# CLK_Mezzanine.net
KiCad netlist of a schematic drawn in Altium Designer
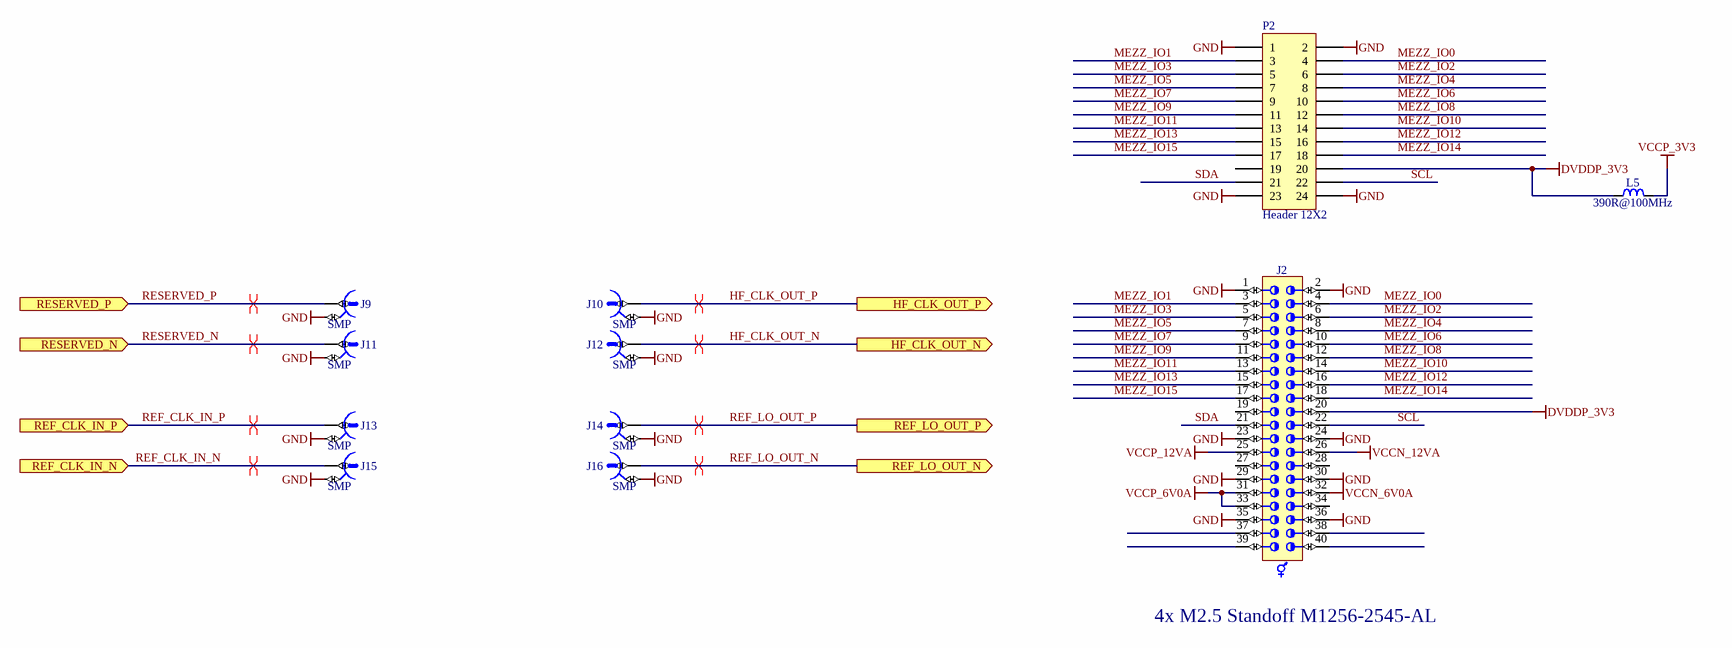
[diagram p0: CLK_Mezzanine.SchDoc]

(export (version "E")
  (design (tool "Eeschema 10.0.6"))
  (components
    (comp (ref "J2")
      (value "~")
      (footprint "SAMTEC_LSS-120-03-L-DV-A")
      (description "Connector 40 Hermaphroditic")
      (fields
        (field (name "PART NUMBER") "SAMTEC_LSS-120-03-L-DV-A")
        (field (name "MANUFACTURER") "SAMTEC")
        (field (name "AUTHOR") "CERN DEM JMW")
      )
      (libsource (lib "Connectors") (part "Connector 40 Hermaphroditic"))
    )
    (comp (ref "J9")
      (value "SMP")
      (footprint "MOLEX_85305-0232")
      (fields
        (field (name "PART NUMBER") "MOLEX_85305-0232")
        (field (name "MANUFACTURER") "MOLEX")
        (field (name "MANUFACTURER PART NUMBER") "85305-0232")
        (field (name "AUTHOR") "CERN DEM JMW")
      )
      (libsource (lib "") (part "Coax_1Male_1Shield_1"))
    )
    (comp (ref "J10")
      (value "SMP")
      (footprint "MOLEX_85305-0232")
      (fields
        (field (name "PART NUMBER") "MOLEX_85305-0232")
        (field (name "MANUFACTURER") "MOLEX")
        (field (name "MANUFACTURER PART NUMBER") "85305-0232")
        (field (name "AUTHOR") "CERN DEM JMW")
      )
      (libsource (lib "Connectors") (part "Coax_1Male_1Shield"))
    )
    (comp (ref "J11")
      (value "SMP")
      (footprint "MOLEX_85305-0232")
      (fields
        (field (name "PART NUMBER") "MOLEX_85305-0232")
        (field (name "MANUFACTURER") "MOLEX")
        (field (name "MANUFACTURER PART NUMBER") "85305-0232")
        (field (name "AUTHOR") "CERN DEM JMW")
      )
      (libsource (lib "") (part "Coax_1Male_1Shield_1"))
    )
    (comp (ref "J12")
      (value "SMP")
      (footprint "MOLEX_85305-0232")
      (fields
        (field (name "PART NUMBER") "MOLEX_85305-0232")
        (field (name "MANUFACTURER") "MOLEX")
        (field (name "MANUFACTURER PART NUMBER") "85305-0232")
        (field (name "AUTHOR") "CERN DEM JMW")
      )
      (libsource (lib "Connectors") (part "Coax_1Male_1Shield"))
    )
    (comp (ref "J13")
      (value "SMP")
      (footprint "MOLEX_85305-0232")
      (fields
        (field (name "PART NUMBER") "MOLEX_85305-0232")
        (field (name "MANUFACTURER") "MOLEX")
        (field (name "MANUFACTURER PART NUMBER") "85305-0232")
        (field (name "AUTHOR") "CERN DEM JMW")
      )
      (libsource (lib "") (part "Coax_1Male_1Shield_1"))
    )
    (comp (ref "J14")
      (value "SMP")
      (footprint "MOLEX_85305-0232")
      (fields
        (field (name "PART NUMBER") "MOLEX_85305-0232")
        (field (name "MANUFACTURER") "MOLEX")
        (field (name "MANUFACTURER PART NUMBER") "85305-0232")
        (field (name "AUTHOR") "CERN DEM JMW")
      )
      (libsource (lib "Connectors") (part "Coax_1Male_1Shield"))
    )
    (comp (ref "J15")
      (value "SMP")
      (footprint "MOLEX_85305-0232")
      (fields
        (field (name "PART NUMBER") "MOLEX_85305-0232")
        (field (name "MANUFACTURER") "MOLEX")
        (field (name "MANUFACTURER PART NUMBER") "85305-0232")
        (field (name "AUTHOR") "CERN DEM JMW")
      )
      (libsource (lib "") (part "Coax_1Male_1Shield_1"))
    )
    (comp (ref "J16")
      (value "SMP")
      (footprint "MOLEX_85305-0232")
      (fields
        (field (name "PART NUMBER") "MOLEX_85305-0232")
        (field (name "MANUFACTURER") "MOLEX")
        (field (name "MANUFACTURER PART NUMBER") "85305-0232")
        (field (name "AUTHOR") "CERN DEM JMW")
      )
      (libsource (lib "Connectors") (part "Coax_1Male_1Shield"))
    )
    (comp (ref "L5")
      (value "390R@100MHz")
      (footprint "INDC1608X95N")
      (description "Inductor")
      (fields
        (field (name "PART NUMBER") "IND0603_TDK_MPZ1608R391A")
        (field (name "POWER") "1.2A")
        (field (name "AUTHOR") "CERN DEM JLC")
      )
      (libsource (lib "Inductors & Transformers") (part "Inductor"))
    )
    (comp (ref "P2")
      (value "Header 12X2")
      (footprint "HDR2X12")
      (description "Header, 12-Pin, Dual row")
      (fields (field (name "PUBLISHER") "Altium Limited"))
      (libsource (lib "Miscellaneous Connectors") (part "Header 12X2"))
    )
  )
  (nets
    (net (code "1") (name "/HF_CLK_OUT_N") (class "Default")
      (node (ref "J12") (pin "1") (pinfunction "1_1") (pintype "bidirectional"))
    )
    (net (code "2") (name "/HF_CLK_OUT_P") (class "Default")
      (node (ref "J10") (pin "1") (pinfunction "1_1") (pintype "bidirectional"))
    )
    (net (code "3") (name "/MEZZ_IO0") (class "Default")
      (node (ref "J2") (pin "4") (pinfunction "4_4") (pintype "bidirectional"))
      (node (ref "P2") (pin "4") (pinfunction "4_4") (pintype "passive"))
    )
    (net (code "4") (name "/MEZZ_IO1") (class "Default")
      (node (ref "J2") (pin "3") (pinfunction "3_3") (pintype "bidirectional"))
      (node (ref "P2") (pin "3") (pinfunction "3_3") (pintype "passive"))
    )
    (net (code "5") (name "/MEZZ_IO2") (class "Default")
      (node (ref "J2") (pin "6") (pinfunction "6_6") (pintype "bidirectional"))
      (node (ref "P2") (pin "6") (pinfunction "6_6") (pintype "passive"))
    )
    (net (code "6") (name "/MEZZ_IO3") (class "Default")
      (node (ref "J2") (pin "5") (pinfunction "5_5") (pintype "bidirectional"))
      (node (ref "P2") (pin "5") (pinfunction "5_5") (pintype "passive"))
    )
    (net (code "7") (name "/MEZZ_IO4") (class "Default")
      (node (ref "J2") (pin "8") (pinfunction "8_8") (pintype "bidirectional"))
      (node (ref "P2") (pin "8") (pinfunction "8_8") (pintype "passive"))
    )
    (net (code "8") (name "/MEZZ_IO5") (class "Default")
      (node (ref "J2") (pin "7") (pinfunction "7_7") (pintype "bidirectional"))
      (node (ref "P2") (pin "7") (pinfunction "7_7") (pintype "passive"))
    )
    (net (code "9") (name "/MEZZ_IO6") (class "Default")
      (node (ref "J2") (pin "10") (pinfunction "10_10") (pintype "bidirectional"))
      (node (ref "P2") (pin "10") (pinfunction "10_10") (pintype "passive"))
    )
    (net (code "10") (name "/MEZZ_IO7") (class "Default")
      (node (ref "J2") (pin "9") (pinfunction "9_9") (pintype "bidirectional"))
      (node (ref "P2") (pin "9") (pinfunction "9_9") (pintype "passive"))
    )
    (net (code "11") (name "/MEZZ_IO8") (class "Default")
      (node (ref "J2") (pin "12") (pinfunction "12_12") (pintype "bidirectional"))
      (node (ref "P2") (pin "12") (pinfunction "12_12") (pintype "passive"))
    )
    (net (code "12") (name "/MEZZ_IO9") (class "Default")
      (node (ref "J2") (pin "11") (pinfunction "11_11") (pintype "bidirectional"))
      (node (ref "P2") (pin "11") (pinfunction "11_11") (pintype "passive"))
    )
    (net (code "13") (name "/MEZZ_IO10") (class "Default")
      (node (ref "J2") (pin "14") (pinfunction "14_14") (pintype "bidirectional"))
      (node (ref "P2") (pin "14") (pinfunction "14_14") (pintype "passive"))
    )
    (net (code "14") (name "/MEZZ_IO11") (class "Default")
      (node (ref "J2") (pin "13") (pinfunction "13_13") (pintype "bidirectional"))
      (node (ref "P2") (pin "13") (pinfunction "13_13") (pintype "passive"))
    )
    (net (code "15") (name "/MEZZ_IO12") (class "Default")
      (node (ref "J2") (pin "16") (pinfunction "16_16") (pintype "bidirectional"))
      (node (ref "P2") (pin "16") (pinfunction "16_16") (pintype "passive"))
    )
    (net (code "16") (name "/MEZZ_IO13") (class "Default")
      (node (ref "J2") (pin "15") (pinfunction "15_15") (pintype "bidirectional"))
      (node (ref "P2") (pin "15") (pinfunction "15_15") (pintype "passive"))
    )
    (net (code "17") (name "/MEZZ_IO14") (class "Default")
      (node (ref "J2") (pin "18") (pinfunction "18_18") (pintype "bidirectional"))
      (node (ref "P2") (pin "18") (pinfunction "18_18") (pintype "passive"))
    )
    (net (code "18") (name "/MEZZ_IO15") (class "Default")
      (node (ref "J2") (pin "17") (pinfunction "17_17") (pintype "bidirectional"))
      (node (ref "P2") (pin "17") (pinfunction "17_17") (pintype "passive"))
    )
    (net (code "19") (name "/REF_CLK_IN_N") (class "Default")
      (node (ref "J15") (pin "1") (pinfunction "1_1") (pintype "bidirectional"))
    )
    (net (code "20") (name "/REF_CLK_IN_P") (class "Default")
      (node (ref "J13") (pin "1") (pinfunction "1_1") (pintype "bidirectional"))
    )
    (net (code "21") (name "/REF_LO_OUT_N") (class "Default")
      (node (ref "J16") (pin "1") (pinfunction "1_1") (pintype "bidirectional"))
    )
    (net (code "22") (name "/REF_LO_OUT_P") (class "Default")
      (node (ref "J14") (pin "1") (pinfunction "1_1") (pintype "bidirectional"))
    )
    (net (code "23") (name "/RESERVED_N") (class "Default")
      (node (ref "J11") (pin "1") (pinfunction "1_1") (pintype "bidirectional"))
    )
    (net (code "24") (name "/RESERVED_P") (class "Default")
      (node (ref "J9") (pin "1") (pinfunction "1_1") (pintype "bidirectional"))
    )
    (net (code "25") (name "/SCL") (class "Default")
      (node (ref "J2") (pin "22") (pinfunction "22_22") (pintype "bidirectional"))
      (node (ref "P2") (pin "22") (pinfunction "22_22") (pintype "passive"))
    )
    (net (code "26") (name "/SDA") (class "Default")
      (node (ref "J2") (pin "21") (pinfunction "21_21") (pintype "bidirectional"))
      (node (ref "P2") (pin "21") (pinfunction "21_21") (pintype "passive"))
    )
    (net (code "27") (name "DVDDP_3V3") (class "Default")
      (node (ref "J2") (pin "20") (pinfunction "20_20") (pintype "bidirectional"))
      (node (ref "L5") (pin "1") (pinfunction "1_1") (pintype "passive"))
      (node (ref "P2") (pin "20") (pinfunction "20_20") (pintype "passive"))
    )
    (net (code "28") (name "GND") (class "Default")
      (node (ref "J10") (pin "2") (pinfunction "2_2") (pintype "bidirectional"))
      (node (ref "J11") (pin "2") (pinfunction "2_2") (pintype "bidirectional"))
      (node (ref "J12") (pin "2") (pinfunction "2_2") (pintype "bidirectional"))
      (node (ref "J13") (pin "2") (pinfunction "2_2") (pintype "bidirectional"))
      (node (ref "J14") (pin "2") (pinfunction "2_2") (pintype "bidirectional"))
      (node (ref "J15") (pin "2") (pinfunction "2_2") (pintype "bidirectional"))
      (node (ref "J16") (pin "2") (pinfunction "2_2") (pintype "bidirectional"))
      (node (ref "J2") (pin "1") (pinfunction "1_1") (pintype "bidirectional"))
      (node (ref "J2") (pin "2") (pinfunction "2_2") (pintype "bidirectional"))
      (node (ref "J2") (pin "23") (pinfunction "23_23") (pintype "bidirectional"))
      (node (ref "J2") (pin "24") (pinfunction "24_24") (pintype "bidirectional"))
      (node (ref "J2") (pin "29") (pinfunction "29_29") (pintype "bidirectional"))
      (node (ref "J2") (pin "30") (pinfunction "30_30") (pintype "bidirectional"))
      (node (ref "J2") (pin "35") (pinfunction "35_35") (pintype "bidirectional"))
      (node (ref "J2") (pin "36") (pinfunction "36_36") (pintype "bidirectional"))
      (node (ref "J9") (pin "2") (pinfunction "2_2") (pintype "bidirectional"))
      (node (ref "P2") (pin "1") (pinfunction "1_1") (pintype "passive"))
      (node (ref "P2") (pin "2") (pinfunction "2_2") (pintype "passive"))
      (node (ref "P2") (pin "23") (pinfunction "23_23") (pintype "passive"))
      (node (ref "P2") (pin "24") (pinfunction "24_24") (pintype "passive"))
    )
    (net (code "29") (name "VCCN_6V0A") (class "Default")
      (node (ref "J2") (pin "32") (pinfunction "32_32") (pintype "bidirectional"))
    )
    (net (code "30") (name "VCCN_12VA") (class "Default")
      (node (ref "J2") (pin "26") (pinfunction "26_26") (pintype "bidirectional"))
    )
    (net (code "31") (name "VCCP_3V3") (class "Default")
      (node (ref "L5") (pin "2") (pinfunction "2_2") (pintype "passive"))
    )
    (net (code "32") (name "VCCP_6V0A") (class "Default")
      (node (ref "J2") (pin "31") (pinfunction "31_31") (pintype "bidirectional"))
      (node (ref "J2") (pin "33") (pinfunction "33_33") (pintype "bidirectional"))
    )
    (net (code "33") (name "VCCP_12VA") (class "Default")
      (node (ref "J2") (pin "25") (pinfunction "25_25") (pintype "bidirectional"))
    )
    (net (code "34") (name "unconnected-(J2-Pad19)") (class "Default")
      (node (ref "J2") (pin "19") (pinfunction "19_19") (pintype "bidirectional"))
    )
    (net (code "35") (name "unconnected-(J2-Pad27)") (class "Default")
      (node (ref "J2") (pin "27") (pinfunction "27_27") (pintype "bidirectional"))
    )
    (net (code "36") (name "unconnected-(J2-Pad28)") (class "Default")
      (node (ref "J2") (pin "28") (pinfunction "28_28") (pintype "bidirectional"))
    )
    (net (code "37") (name "unconnected-(J2-Pad34)") (class "Default")
      (node (ref "J2") (pin "34") (pinfunction "34_34") (pintype "bidirectional"))
    )
    (net (code "38") (name "unconnected-(J2-Pad37)") (class "Default")
      (node (ref "J2") (pin "37") (pinfunction "37_37") (pintype "bidirectional"))
    )
    (net (code "39") (name "unconnected-(J2-Pad38)") (class "Default")
      (node (ref "J2") (pin "38") (pinfunction "38_38") (pintype "bidirectional"))
    )
    (net (code "40") (name "unconnected-(J2-Pad39)") (class "Default")
      (node (ref "J2") (pin "39") (pinfunction "39_39") (pintype "bidirectional"))
    )
    (net (code "41") (name "unconnected-(J2-Pad40)") (class "Default")
      (node (ref "J2") (pin "40") (pinfunction "40_40") (pintype "bidirectional"))
    )
    (net (code "42") (name "unconnected-(P2-Pad19)") (class "Default")
      (node (ref "P2") (pin "19") (pinfunction "19_19") (pintype "passive"))
    )
  )
)
